# tube-socket-in-8.net
KiCad netlist of a schematic drawn in Altium Designer
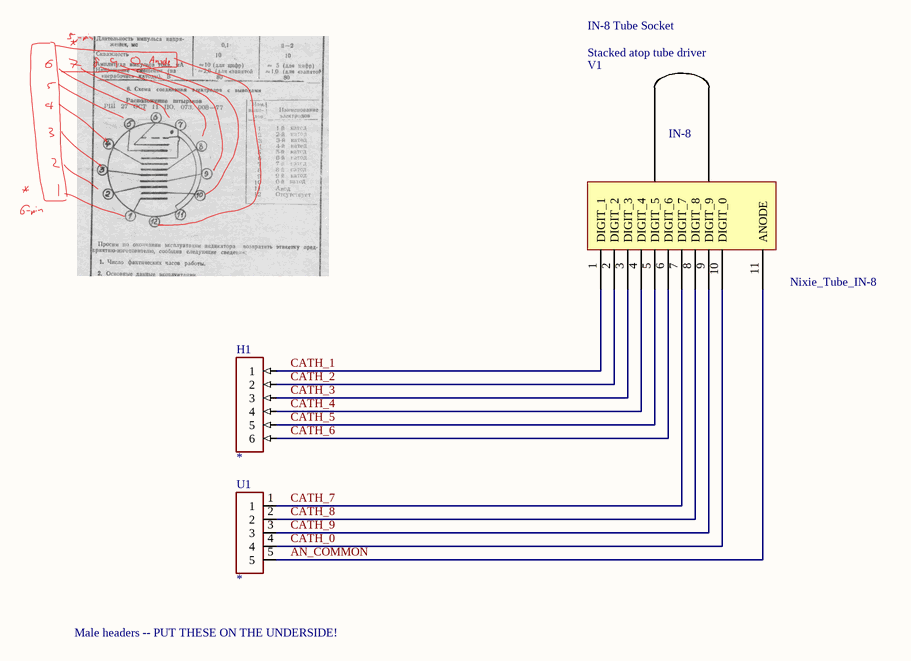
[diagram p0: tube-socket-in-8.SchDoc]

(export (version "E")
  (design (tool "Eeschema 10.0.6"))
  (components
    (comp (ref "H1")
      (value "2.54-1x6P")
      (footprint "2.54-1x6P")
      (fields
        (field (name "ALTIUM_VALUE") "*")
        (field (name "JLCPCB PART #") "C37208")
        (field (name "MANUFACTURER") "BOOMELE(Boom Precision Elec)")
      )
      (libsource (lib "2.54-1x6P") (part "2.54-1x6P"))
    )
    (comp (ref "U1")
      (value "HX PZ2.54-1x5P ZZ")
      (footprint "HX PZ2.54-1x5P ZZ")
      (fields
        (field (name "ALTIUM_VALUE") "*")
        (field (name "JLCPCB PART #") "C32713271")
        (field (name "MANUFACTURER") "hanxia")
      )
      (libsource (lib "HX PZ2.54-1x5P ZZ") (part "HX PZ2.54-1x5P ZZ"))
    )
    (comp (ref "V1")
      (value "Nixie_Tube_IN-8")
      (footprint "Nixie_Tube_IN-8")
      (libsource (lib "Nixie_Tube_IN-8") (part "Nixie_Tube_IN-8"))
    )
  )
  (nets
    (net (code "1") (name "/AN_COMMON") (class "Default")
      (node (ref "U1") (pin "5") (pinfunction "5_5") (pintype "passive"))
      (node (ref "V1") (pin "11") (pinfunction "ANODE_11") (pintype "passive"))
    )
    (net (code "2") (name "/CATH_0") (class "Default")
      (node (ref "U1") (pin "4") (pinfunction "4_4") (pintype "passive"))
      (node (ref "V1") (pin "10") (pinfunction "DIGIT_0_10") (pintype "passive"))
    )
    (net (code "3") (name "/CATH_1") (class "Default")
      (node (ref "H1") (pin "1") (pinfunction "1_1") (pintype "input"))
      (node (ref "V1") (pin "1") (pinfunction "DIGIT_1_1") (pintype "passive"))
    )
    (net (code "4") (name "/CATH_2") (class "Default")
      (node (ref "H1") (pin "2") (pinfunction "2_2") (pintype "input"))
      (node (ref "V1") (pin "2") (pinfunction "DIGIT_2_2") (pintype "passive"))
    )
    (net (code "5") (name "/CATH_3") (class "Default")
      (node (ref "H1") (pin "3") (pinfunction "3_3") (pintype "input"))
      (node (ref "V1") (pin "3") (pinfunction "DIGIT_3_3") (pintype "passive"))
    )
    (net (code "6") (name "/CATH_4") (class "Default")
      (node (ref "H1") (pin "4") (pinfunction "4_4") (pintype "input"))
      (node (ref "V1") (pin "4") (pinfunction "DIGIT_4_4") (pintype "passive"))
    )
    (net (code "7") (name "/CATH_5") (class "Default")
      (node (ref "H1") (pin "5") (pinfunction "5_5") (pintype "input"))
      (node (ref "V1") (pin "5") (pinfunction "DIGIT_5_5") (pintype "passive"))
    )
    (net (code "8") (name "/CATH_6") (class "Default")
      (node (ref "H1") (pin "6") (pinfunction "6_6") (pintype "input"))
      (node (ref "V1") (pin "6") (pinfunction "DIGIT_6_6") (pintype "passive"))
    )
    (net (code "9") (name "/CATH_7") (class "Default")
      (node (ref "U1") (pin "1") (pinfunction "1_1") (pintype "passive"))
      (node (ref "V1") (pin "7") (pinfunction "DIGIT_7_7") (pintype "passive"))
    )
    (net (code "10") (name "/CATH_8") (class "Default")
      (node (ref "U1") (pin "2") (pinfunction "2_2") (pintype "passive"))
      (node (ref "V1") (pin "8") (pinfunction "DIGIT_8_8") (pintype "passive"))
    )
    (net (code "11") (name "/CATH_9") (class "Default")
      (node (ref "U1") (pin "3") (pinfunction "3_3") (pintype "passive"))
      (node (ref "V1") (pin "9") (pinfunction "DIGIT_9_9") (pintype "passive"))
    )
  )
)
